# Sheet1.net
KiCad netlist of a schematic drawn in Altium Designer
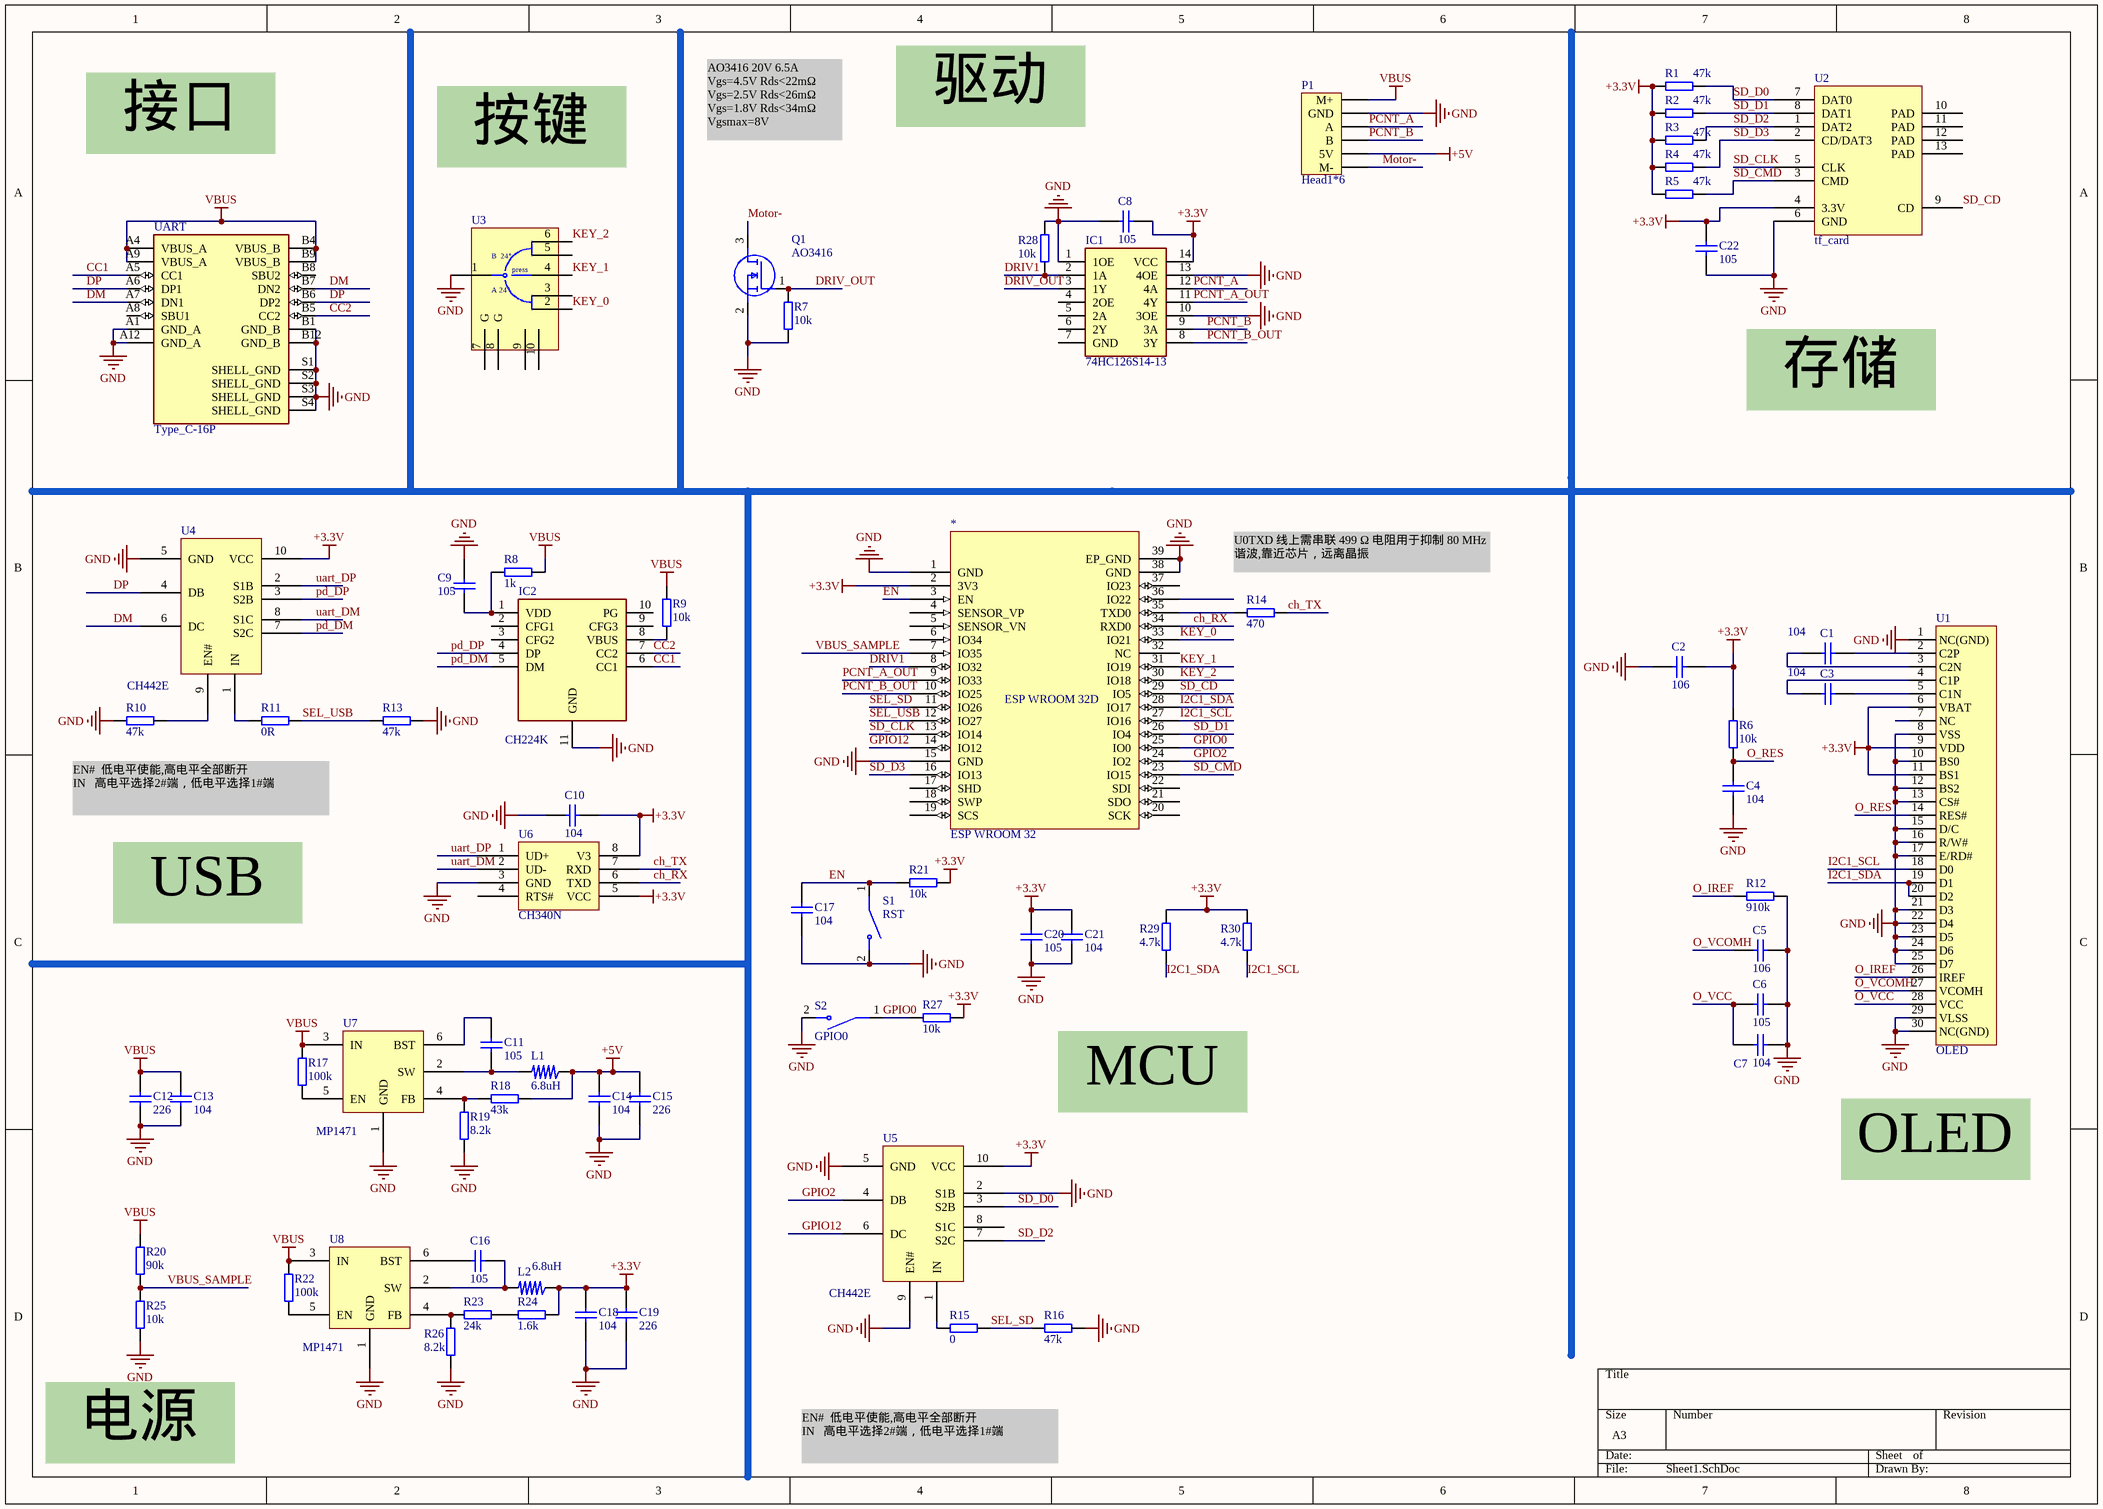
[diagram p0: Sheet1.SchDoc]

(export (version "E")
  (design (tool "Eeschema 10.0.6"))
  (components
    (comp (ref "*")
      (value "ESP WROOM 32")
      (footprint "ESP32-WROOM-32D")
      (libsource (lib "BuildDev") (part "ESP WROOM 32"))
    )
    (comp (ref "C1")
      (value "104")
      (footprint "CAPC1608[0603]")
      (description "Chip Capacitor, PSpice Model")
      (fields
        (field (name "TOLERANCE") "Y5V")
        (field (name "VOLTAGE") "3V")
        (field (name "PUBLISHER") "Altium Limited")
      )
      (libsource (lib "!)Miscellaneous Integrated Library") (part "Cap Chip 1"))
    )
    (comp (ref "C2")
      (value "106")
      (footprint "CAPC1608[0603]")
      (description "Chip Capacitor, PSpice Model")
      (fields
        (field (name "TOLERANCE") "Y5V")
        (field (name "VOLTAGE") "3V")
        (field (name "PUBLISHER") "Altium Limited")
      )
      (libsource (lib "!)Miscellaneous Integrated Library") (part "Cap Chip 1"))
    )
    (comp (ref "C3")
      (value "104")
      (footprint "CAPC1608[0603]")
      (description "Chip Capacitor, PSpice Model")
      (fields
        (field (name "TOLERANCE") "Y5V")
        (field (name "VOLTAGE") "3V")
        (field (name "PUBLISHER") "Altium Limited")
      )
      (libsource (lib "!)Miscellaneous Integrated Library") (part "Cap Chip 1"))
    )
    (comp (ref "C4")
      (value "104")
      (footprint "CAPC1608[0603]")
      (description "Chip Capacitor, PSpice Model")
      (fields
        (field (name "TOLERANCE") "Y5V")
        (field (name "VOLTAGE") "3V")
        (field (name "PUBLISHER") "Altium Limited")
      )
      (libsource (lib "!)Miscellaneous Integrated Library") (part "Cap Chip 1"))
    )
    (comp (ref "C5")
      (value "106")
      (footprint "CAPC1608[0603]")
      (description "Chip Capacitor, PSpice Model")
      (fields
        (field (name "TOLERANCE") "Y5V")
        (field (name "VOLTAGE") "3V")
        (field (name "PUBLISHER") "Altium Limited")
      )
      (libsource (lib "!)Miscellaneous Integrated Library") (part "Cap Chip 1"))
    )
    (comp (ref "C6")
      (value "105")
      (footprint "CAPC1608[0603]")
      (description "Chip Capacitor, PSpice Model")
      (fields
        (field (name "TOLERANCE") "Y5V")
        (field (name "VOLTAGE") "3V")
        (field (name "PUBLISHER") "Altium Limited")
      )
      (libsource (lib "!)Miscellaneous Integrated Library") (part "Cap Chip 1"))
    )
    (comp (ref "C7")
      (value "104")
      (footprint "CAPC1608[0603]")
      (description "Chip Capacitor, PSpice Model")
      (fields
        (field (name "TOLERANCE") "Y5V")
        (field (name "VOLTAGE") "3V")
        (field (name "PUBLISHER") "Altium Limited")
      )
      (libsource (lib "!)Miscellaneous Integrated Library") (part "Cap Chip 1"))
    )
    (comp (ref "C8")
      (value "105")
      (footprint "CAPC1608[0603]")
      (description "Chip Capacitor, PSpice Model")
      (fields
        (field (name "TOLERANCE") "Y5V")
        (field (name "VOLTAGE") "3V")
        (field (name "PUBLISHER") "Altium Limited")
      )
      (libsource (lib "!)Miscellaneous Integrated Library") (part "Cap Chip 1"))
    )
    (comp (ref "C9")
      (value "105")
      (footprint "CAPC1608[0603]")
      (description "Chip Capacitor, PSpice Model")
      (fields
        (field (name "TOLERANCE") "Y5V")
        (field (name "VOLTAGE") "3V")
        (field (name "PUBLISHER") "Altium Limited")
      )
      (libsource (lib "!)Miscellaneous Integrated Library") (part "Cap Chip 1"))
    )
    (comp (ref "C10")
      (value "104")
      (footprint "CAPC1608[0603]")
      (description "Chip Capacitor, PSpice Model")
      (fields
        (field (name "TOLERANCE") "Y5V")
        (field (name "VOLTAGE") "3V")
        (field (name "PUBLISHER") "Altium Limited")
      )
      (libsource (lib "!)Miscellaneous Integrated Library") (part "Cap Chip 1"))
    )
    (comp (ref "C11")
      (value "105")
      (footprint "CAPC1608[0603]")
      (description "Chip Capacitor, PSpice Model")
      (fields
        (field (name "TOLERANCE") "Y5V")
        (field (name "VOLTAGE") "3V")
        (field (name "PUBLISHER") "Altium Limited")
      )
      (libsource (lib "!)Miscellaneous Integrated Library") (part "Cap Chip 1"))
    )
    (comp (ref "C12")
      (value "226")
      (footprint "CAPC1608[0603]")
      (description "Chip Capacitor, PSpice Model")
      (fields
        (field (name "TOLERANCE") "Y5V")
        (field (name "VOLTAGE") "3V")
        (field (name "PUBLISHER") "Altium Limited")
      )
      (libsource (lib "!)Miscellaneous Integrated Library") (part "Cap Chip 1"))
    )
    (comp (ref "C13")
      (value "104")
      (footprint "CAPC1608[0603]")
      (description "Chip Capacitor, PSpice Model")
      (fields
        (field (name "TOLERANCE") "Y5V")
        (field (name "VOLTAGE") "3V")
        (field (name "PUBLISHER") "Altium Limited")
      )
      (libsource (lib "!)Miscellaneous Integrated Library") (part "Cap Chip 1"))
    )
    (comp (ref "C14")
      (value "104")
      (footprint "CAPC1608[0603]")
      (description "Chip Capacitor, PSpice Model")
      (fields
        (field (name "TOLERANCE") "Y5V")
        (field (name "VOLTAGE") "3V")
        (field (name "PUBLISHER") "Altium Limited")
      )
      (libsource (lib "!)Miscellaneous Integrated Library") (part "Cap Chip 1"))
    )
    (comp (ref "C15")
      (value "226")
      (footprint "CAPC1608[0603]")
      (description "Chip Capacitor, PSpice Model")
      (fields
        (field (name "TOLERANCE") "Y5V")
        (field (name "VOLTAGE") "3V")
        (field (name "PUBLISHER") "Altium Limited")
      )
      (libsource (lib "!)Miscellaneous Integrated Library") (part "Cap Chip 1"))
    )
    (comp (ref "C16")
      (value "105")
      (footprint "CAPC1608[0603]")
      (description "Chip Capacitor, PSpice Model")
      (fields
        (field (name "TOLERANCE") "Y5V")
        (field (name "VOLTAGE") "3V")
        (field (name "PUBLISHER") "Altium Limited")
      )
      (libsource (lib "!)Miscellaneous Integrated Library") (part "Cap Chip 1"))
    )
    (comp (ref "C17")
      (value "104")
      (footprint "CAPC1608[0603]")
      (description "Chip Capacitor, PSpice Model")
      (fields
        (field (name "TOLERANCE") "Y5V")
        (field (name "VOLTAGE") "3V")
        (field (name "PUBLISHER") "Altium Limited")
      )
      (libsource (lib "!)Miscellaneous Integrated Library") (part "Cap Chip 1"))
    )
    (comp (ref "C18")
      (value "104")
      (footprint "CAPC1608[0603]")
      (description "Chip Capacitor, PSpice Model")
      (fields
        (field (name "TOLERANCE") "Y5V")
        (field (name "VOLTAGE") "3V")
        (field (name "PUBLISHER") "Altium Limited")
      )
      (libsource (lib "!)Miscellaneous Integrated Library") (part "Cap Chip 1"))
    )
    (comp (ref "C19")
      (value "226")
      (footprint "CAPC1608[0603]")
      (description "Chip Capacitor, PSpice Model")
      (fields
        (field (name "TOLERANCE") "Y5V")
        (field (name "VOLTAGE") "3V")
        (field (name "PUBLISHER") "Altium Limited")
      )
      (libsource (lib "!)Miscellaneous Integrated Library") (part "Cap Chip 1"))
    )
    (comp (ref "C20")
      (value "105")
      (footprint "CAPC1608[0603]")
      (description "Chip Capacitor, PSpice Model")
      (fields
        (field (name "TOLERANCE") "Y5V")
        (field (name "VOLTAGE") "3V")
        (field (name "PUBLISHER") "Altium Limited")
      )
      (libsource (lib "!)Miscellaneous Integrated Library") (part "Cap Chip 1"))
    )
    (comp (ref "C21")
      (value "104")
      (footprint "CAPC1608[0603]")
      (description "Chip Capacitor, PSpice Model")
      (fields
        (field (name "TOLERANCE") "Y5V")
        (field (name "VOLTAGE") "3V")
        (field (name "PUBLISHER") "Altium Limited")
      )
      (libsource (lib "!)Miscellaneous Integrated Library") (part "Cap Chip 1"))
    )
    (comp (ref "C22")
      (value "105")
      (footprint "CAPC1608[0603]")
      (description "Chip Capacitor, PSpice Model")
      (fields
        (field (name "TOLERANCE") "Y5V")
        (field (name "VOLTAGE") "3V")
        (field (name "PUBLISHER") "Altium Limited")
      )
      (libsource (lib "!)Miscellaneous Integrated Library") (part "Cap Chip 1"))
    )
    (comp (ref "IC1")
      (value "74HC126S14-13")
      (footprint "SOIC127P600X173-14N")
      (description "Integrated Circuit")
      (fields (field (name "MOUSER PART NUMBER") "621-74HC126S14-13"))
      (libsource (lib "SamacSys") (part "74HC126S14-13"))
    )
    (comp (ref "IC2")
      (value "CH224K")
      (footprint "SOP100P600X180-11N")
      (description "Integrated Circuit")
      (libsource (lib "SamacSys") (part "CH224K"))
    )
    (comp (ref "L1") (value "6.8uH") (footprint "WHC0420") (libsource (lib "BuildDev") (part "L")))
    (comp (ref "L2") (value "6.8uH") (footprint "WHC0420") (libsource (lib "BuildDev") (part "L")))
    (comp (ref "P1")
      (value "Head1*6")
      (footprint "Header1*6")
      (libsource (lib "BuildDev") (part "Header1x6"))
    )
    (comp (ref "Q1")
      (value "AO3416")
      (footprint "SOT95P237X112-3N")
      (description "MOSFET (N-Channel)")
      (libsource (lib "SamacSys") (part "AO3416"))
    )
    (comp (ref "R1")
      (value "47k")
      (footprint "RESC1608[0603]")
      (description "Chip Resistor, PSpice Model, IPC PCB Library Drawing")
      (fields (field (name "TOLERANCE") "5%") (field (name "PUBLISHER") "Altium Limited"))
      (libsource (lib "!)Miscellaneous Integrated Library") (part "Res Chip 2p 1"))
    )
    (comp (ref "R2")
      (value "47k")
      (footprint "RESC1608[0603]")
      (description "Chip Resistor, PSpice Model, IPC PCB Library Drawing")
      (fields (field (name "TOLERANCE") "5%") (field (name "PUBLISHER") "Altium Limited"))
      (libsource (lib "!)Miscellaneous Integrated Library") (part "Res Chip 2p 1"))
    )
    (comp (ref "R3")
      (value "47k")
      (footprint "RESC1608[0603]")
      (description "Chip Resistor, PSpice Model, IPC PCB Library Drawing")
      (fields (field (name "TOLERANCE") "5%") (field (name "PUBLISHER") "Altium Limited"))
      (libsource (lib "!)Miscellaneous Integrated Library") (part "Res Chip 2p 1"))
    )
    (comp (ref "R4")
      (value "47k")
      (footprint "RESC1608[0603]")
      (description "Chip Resistor, PSpice Model, IPC PCB Library Drawing")
      (fields (field (name "TOLERANCE") "5%") (field (name "PUBLISHER") "Altium Limited"))
      (libsource (lib "!)Miscellaneous Integrated Library") (part "Res Chip 2p 1"))
    )
    (comp (ref "R5")
      (value "47k")
      (footprint "RESC1608[0603]")
      (description "Chip Resistor, PSpice Model, IPC PCB Library Drawing")
      (fields (field (name "TOLERANCE") "5%") (field (name "PUBLISHER") "Altium Limited"))
      (libsource (lib "!)Miscellaneous Integrated Library") (part "Res Chip 2p 1"))
    )
    (comp (ref "R6")
      (value "10k")
      (footprint "RESC1608[0603]")
      (description "Chip Resistor, PSpice Model, IPC PCB Library Drawing")
      (fields (field (name "TOLERANCE") "5%") (field (name "PUBLISHER") "Altium Limited"))
      (libsource (lib "!)Miscellaneous Integrated Library") (part "Res Chip 2p 1"))
    )
    (comp (ref "R7")
      (value "10k")
      (footprint "RESC1608[0603]")
      (description "Chip Resistor, PSpice Model, IPC PCB Library Drawing")
      (fields (field (name "TOLERANCE") "5%") (field (name "PUBLISHER") "Altium Limited"))
      (libsource (lib "!)Miscellaneous Integrated Library") (part "Res Chip 2p 1"))
    )
    (comp (ref "R8")
      (value "1k")
      (footprint "RESC1608[0603]")
      (description "Chip Resistor, PSpice Model, IPC PCB Library Drawing")
      (fields (field (name "TOLERANCE") "5%") (field (name "PUBLISHER") "Altium Limited"))
      (libsource (lib "!)Miscellaneous Integrated Library") (part "Res Chip 2p 1"))
    )
    (comp (ref "R9")
      (value "10k")
      (footprint "RESC1608[0603]")
      (description "Chip Resistor, PSpice Model, IPC PCB Library Drawing")
      (fields (field (name "TOLERANCE") "5%") (field (name "PUBLISHER") "Altium Limited"))
      (libsource (lib "!)Miscellaneous Integrated Library") (part "Res Chip 2p 1"))
    )
    (comp (ref "R10")
      (value "47k")
      (footprint "RESC1608[0603]")
      (description "Chip Resistor, PSpice Model, IPC PCB Library Drawing")
      (fields (field (name "TOLERANCE") "5%") (field (name "PUBLISHER") "Altium Limited"))
      (libsource (lib "!)Miscellaneous Integrated Library") (part "Res Chip 2p 1"))
    )
    (comp (ref "R11")
      (value "0R")
      (footprint "RESC1608[0603]")
      (description "Chip Resistor, PSpice Model, IPC PCB Library Drawing")
      (fields (field (name "TOLERANCE") "5%") (field (name "PUBLISHER") "Altium Limited"))
      (libsource (lib "!)Miscellaneous Integrated Library") (part "Res Chip 2p 1"))
    )
    (comp (ref "R12")
      (value "910k")
      (footprint "RESC1608[0603]")
      (description "Chip Resistor, PSpice Model, IPC PCB Library Drawing")
      (fields (field (name "TOLERANCE") "5%") (field (name "PUBLISHER") "Altium Limited"))
      (libsource (lib "!)Miscellaneous Integrated Library") (part "Res Chip 2p 1"))
    )
    (comp (ref "R13")
      (value "47k")
      (footprint "RESC1608[0603]")
      (description "Chip Resistor, PSpice Model, IPC PCB Library Drawing")
      (fields (field (name "TOLERANCE") "5%") (field (name "PUBLISHER") "Altium Limited"))
      (libsource (lib "!)Miscellaneous Integrated Library") (part "Res Chip 2p 1"))
    )
    (comp (ref "R14")
      (value "470")
      (footprint "RESC1608[0603]")
      (description "Chip Resistor, PSpice Model, IPC PCB Library Drawing")
      (fields (field (name "TOLERANCE") "5%") (field (name "PUBLISHER") "Altium Limited"))
      (libsource (lib "!)Miscellaneous Integrated Library") (part "Res Chip 2p 1"))
    )
    (comp (ref "R15")
      (value "0")
      (footprint "RESC1608[0603]")
      (description "Chip Resistor, PSpice Model, IPC PCB Library Drawing")
      (fields (field (name "TOLERANCE") "5%") (field (name "PUBLISHER") "Altium Limited"))
      (libsource (lib "!)Miscellaneous Integrated Library") (part "Res Chip 2p 1"))
    )
    (comp (ref "R16")
      (value "47k")
      (footprint "RESC1608[0603]")
      (description "Chip Resistor, PSpice Model, IPC PCB Library Drawing")
      (fields (field (name "TOLERANCE") "5%") (field (name "PUBLISHER") "Altium Limited"))
      (libsource (lib "!)Miscellaneous Integrated Library") (part "Res Chip 2p 1"))
    )
    (comp (ref "R17")
      (value "100k")
      (footprint "RESC1608[0603]")
      (description "Chip Resistor, PSpice Model, IPC PCB Library Drawing")
      (fields (field (name "TOLERANCE") "5%") (field (name "PUBLISHER") "Altium Limited"))
      (libsource (lib "!)Miscellaneous Integrated Library") (part "Res Chip 2p 1"))
    )
    (comp (ref "R18")
      (value "43k")
      (footprint "RESC1608[0603]")
      (description "Chip Resistor, PSpice Model, IPC PCB Library Drawing")
      (fields (field (name "TOLERANCE") "5%") (field (name "PUBLISHER") "Altium Limited"))
      (libsource (lib "!)Miscellaneous Integrated Library") (part "Res Chip 2p 1"))
    )
    (comp (ref "R19")
      (value "8.2k")
      (footprint "RESC1608[0603]")
      (description "Chip Resistor, PSpice Model, IPC PCB Library Drawing")
      (fields (field (name "TOLERANCE") "5%") (field (name "PUBLISHER") "Altium Limited"))
      (libsource (lib "!)Miscellaneous Integrated Library") (part "Res Chip 2p 1"))
    )
    (comp (ref "R20")
      (value "90k")
      (footprint "RESC1608[0603]")
      (description "Chip Resistor, PSpice Model, IPC PCB Library Drawing")
      (fields (field (name "TOLERANCE") "5%") (field (name "PUBLISHER") "Altium Limited"))
      (libsource (lib "!)Miscellaneous Integrated Library") (part "Res Chip 2p 1"))
    )
    (comp (ref "R21")
      (value "10k")
      (footprint "RESC1608[0603]")
      (description "Chip Resistor, PSpice Model, IPC PCB Library Drawing")
      (fields (field (name "TOLERANCE") "5%") (field (name "PUBLISHER") "Altium Limited"))
      (libsource (lib "!)Miscellaneous Integrated Library") (part "Res Chip 2p 1"))
    )
    (comp (ref "R22")
      (value "100k")
      (footprint "RESC1608[0603]")
      (description "Chip Resistor, PSpice Model, IPC PCB Library Drawing")
      (fields (field (name "TOLERANCE") "5%") (field (name "PUBLISHER") "Altium Limited"))
      (libsource (lib "!)Miscellaneous Integrated Library") (part "Res Chip 2p 1"))
    )
    (comp (ref "R23")
      (value "24k")
      (footprint "RESC1608[0603]")
      (description "Chip Resistor, PSpice Model, IPC PCB Library Drawing")
      (fields (field (name "TOLERANCE") "5%") (field (name "PUBLISHER") "Altium Limited"))
      (libsource (lib "!)Miscellaneous Integrated Library") (part "Res Chip 2p 1"))
    )
    (comp (ref "R24")
      (value "1.6k")
      (footprint "RESC1608[0603]")
      (description "Chip Resistor, PSpice Model, IPC PCB Library Drawing")
      (fields (field (name "TOLERANCE") "5%") (field (name "PUBLISHER") "Altium Limited"))
      (libsource (lib "!)Miscellaneous Integrated Library") (part "Res Chip 2p 1"))
    )
    (comp (ref "R25")
      (value "10k")
      (footprint "RESC1608[0603]")
      (description "Chip Resistor, PSpice Model, IPC PCB Library Drawing")
      (fields (field (name "TOLERANCE") "5%") (field (name "PUBLISHER") "Altium Limited"))
      (libsource (lib "!)Miscellaneous Integrated Library") (part "Res Chip 2p 1"))
    )
    (comp (ref "R26")
      (value "8.2k")
      (footprint "RESC1608[0603]")
      (description "Chip Resistor, PSpice Model, IPC PCB Library Drawing")
      (fields (field (name "TOLERANCE") "5%") (field (name "PUBLISHER") "Altium Limited"))
      (libsource (lib "!)Miscellaneous Integrated Library") (part "Res Chip 2p 1"))
    )
    (comp (ref "R27")
      (value "10k")
      (footprint "RESC1608[0603]")
      (description "Chip Resistor, PSpice Model, IPC PCB Library Drawing")
      (fields (field (name "TOLERANCE") "5%") (field (name "PUBLISHER") "Altium Limited"))
      (libsource (lib "!)Miscellaneous Integrated Library") (part "Res Chip 2p 1"))
    )
    (comp (ref "R28")
      (value "10k")
      (footprint "RESC1608[0603]")
      (description "Chip Resistor, PSpice Model, IPC PCB Library Drawing")
      (fields (field (name "TOLERANCE") "5%") (field (name "PUBLISHER") "Altium Limited"))
      (libsource (lib "!)Miscellaneous Integrated Library") (part "Res Chip 2p 1"))
    )
    (comp (ref "R29")
      (value "4.7k")
      (footprint "RESC1608[0603]")
      (description "Chip Resistor, PSpice Model, IPC PCB Library Drawing")
      (fields (field (name "TOLERANCE") "5%") (field (name "PUBLISHER") "Altium Limited"))
      (libsource (lib "!)Miscellaneous Integrated Library") (part "Res Chip 2p 1"))
    )
    (comp (ref "R30")
      (value "4.7k")
      (footprint "RESC1608[0603]")
      (description "Chip Resistor, PSpice Model, IPC PCB Library Drawing")
      (fields (field (name "TOLERANCE") "5%") (field (name "PUBLISHER") "Altium Limited"))
      (libsource (lib "!)Miscellaneous Integrated Library") (part "Res Chip 2p 1"))
    )
    (comp (ref "S1")
      (value "RST")
      (footprint "SW_B3U-1000P")
      (fields (field (name "MP") "B3U-1000P"))
      (libsource (lib "BuildDev") (part "SW2P"))
    )
    (comp (ref "S2")
      (value "GPIO0")
      (footprint "SW_B3U-1000P")
      (fields (field (name "MP") "B3U-1000P"))
      (libsource (lib "BuildDev") (part "SW2P"))
    )
    (comp (ref "U1") (value "OLED") (footprint "OLED-panel") (libsource (lib "BuildDev") (part "0.96寸OLED")))
    (comp (ref "U2") (value "tf_card") (footprint "TF-1") (libsource (lib "BuildDev") (part "TF- SDIO")))
    (comp (ref "U3") (value "拨码开关") (footprint "FS-1501S-02") (libsource (lib "BuildDev") (part "thumb key")))
    (comp (ref "U4") (value "CH442E") (footprint "MSOP-10") (libsource (lib "BuildDev") (part "CH442E")))
    (comp (ref "U5") (value "CH442E") (footprint "MSOP-10") (libsource (lib "BuildDev") (part "CH442E")))
    (comp (ref "U6")
      (value "CH340N")
      (footprint "SOP8")
      (description "USB to serial chip CH340N")
      (libsource (lib "BuildDev") (part "CH340N"))
    )
    (comp (ref "U7")
      (value "MP1471")
      (footprint "TSOT23-6")
      (description "4.7v-16V Input\r\n16V3A\r\n500K")
      (libsource (lib "BuildDev") (part "MP1471"))
    )
    (comp (ref "U8")
      (value "MP1471")
      (footprint "TSOT23-6")
      (description "4.7v-16V Input\r\n16V3A\r\n500K")
      (libsource (lib "BuildDev") (part "MP1471"))
    )
    (comp (ref "UART")
      (value "Type_C-16P")
      (footprint "VALCON_CSP-USC16-TR")
      (description "CSP-USC16-TR Valcon USB Type C Surface Mount PCB Socket")
      (fields (field (name "MP") "CSP-USC16-TR") (field (name "MF") "Valcon"))
      (libsource (lib "BuildDev") (part "Type_C-16P"))
    )
  )
  (nets
    (net (code "1") (name "+3.3V") (class "Default")
      (node (ref "*") (pin "2") (pinfunction "3V3_2") (pintype "passive"))
      (node (ref "C10") (pin "1") (pinfunction "1_1") (pintype "passive"))
      (node (ref "C18") (pin "1") (pinfunction "1_1") (pintype "passive"))
      (node (ref "C19") (pin "1") (pinfunction "1_1") (pintype "passive"))
      (node (ref "C2") (pin "1") (pinfunction "1_1") (pintype "passive"))
      (node (ref "C20") (pin "1") (pinfunction "1_1") (pintype "passive"))
      (node (ref "C21") (pin "1") (pinfunction "1_1") (pintype "passive"))
      (node (ref "C22") (pin "2") (pinfunction "2_2") (pintype "passive"))
      (node (ref "C8") (pin "2") (pinfunction "2_2") (pintype "passive"))
      (node (ref "IC1") (pin "14") (pinfunction "VCC_14") (pintype "passive"))
      (node (ref "L2") (pin "1") (pinfunction "1_1") (pintype "passive"))
      (node (ref "R1") (pin "2") (pinfunction "2_2") (pintype "passive"))
      (node (ref "R2") (pin "2") (pinfunction "2_2") (pintype "passive"))
      (node (ref "R21") (pin "1") (pinfunction "1_1") (pintype "passive"))
      (node (ref "R24") (pin "2") (pinfunction "2_2") (pintype "passive"))
      (node (ref "R27") (pin "1") (pinfunction "1_1") (pintype "passive"))
      (node (ref "R29") (pin "1") (pinfunction "1_1") (pintype "passive"))
      (node (ref "R3") (pin "2") (pinfunction "2_2") (pintype "passive"))
      (node (ref "R30") (pin "1") (pinfunction "1_1") (pintype "passive"))
      (node (ref "R4") (pin "2") (pinfunction "2_2") (pintype "passive"))
      (node (ref "R5") (pin "2") (pinfunction "2_2") (pintype "passive"))
      (node (ref "R6") (pin "1") (pinfunction "1_1") (pintype "passive"))
      (node (ref "U1") (pin "11") (pinfunction "BS1_11") (pintype "passive"))
      (node (ref "U1") (pin "6") (pinfunction "VBAT_6") (pintype "passive"))
      (node (ref "U1") (pin "9") (pinfunction "VDD_9") (pintype "passive"))
      (node (ref "U2") (pin "4") (pinfunction "3.3V_4") (pintype "passive"))
      (node (ref "U4") (pin "10") (pinfunction "VCC_10") (pintype "passive"))
      (node (ref "U5") (pin "10") (pinfunction "VCC_10") (pintype "passive"))
      (node (ref "U6") (pin "5") (pinfunction "VCC_5") (pintype "passive"))
      (node (ref "U6") (pin "8") (pinfunction "V3_8") (pintype "passive"))
    )
    (net (code "2") (name "+5V") (class "Default")
      (node (ref "C14") (pin "1") (pinfunction "1_1") (pintype "passive"))
      (node (ref "C15") (pin "1") (pinfunction "1_1") (pintype "passive"))
      (node (ref "L1") (pin "1") (pinfunction "1_1") (pintype "passive"))
      (node (ref "P1") (pin "5") (pinfunction "5V_5") (pintype "passive"))
      (node (ref "R18") (pin "2") (pinfunction "2_2") (pintype "passive"))
    )
    (net (code "3") (name "/CC1") (class "Default")
      (node (ref "IC2") (pin "6") (pinfunction "CC1_6") (pintype "passive"))
      (node (ref "UART") (pin "A5") (pinfunction "CC1_A5") (pintype "bidirectional"))
    )
    (net (code "4") (name "/CC2") (class "Default")
      (node (ref "IC2") (pin "7") (pinfunction "CC2_7") (pintype "passive"))
      (node (ref "UART") (pin "B5") (pinfunction "CC2_B5") (pintype "bidirectional"))
    )
    (net (code "5") (name "/DM") (class "Default")
      (node (ref "U4") (pin "6") (pinfunction "DC_6") (pintype "passive"))
      (node (ref "UART") (pin "A7") (pinfunction "DN1_A7") (pintype "bidirectional"))
      (node (ref "UART") (pin "B7") (pinfunction "DN2_B7") (pintype "bidirectional"))
    )
    (net (code "6") (name "/DP") (class "Default")
      (node (ref "U4") (pin "4") (pinfunction "DB_4") (pintype "passive"))
      (node (ref "UART") (pin "A6") (pinfunction "DP1_A6") (pintype "bidirectional"))
      (node (ref "UART") (pin "B6") (pinfunction "DP2_B6") (pintype "bidirectional"))
    )
    (net (code "7") (name "/DRIV1") (class "Default")
      (node (ref "*") (pin "8") (pinfunction "IO32_8") (pintype "bidirectional"))
      (node (ref "IC1") (pin "2") (pinfunction "1A_2") (pintype "passive"))
      (node (ref "R28") (pin "2") (pinfunction "2_2") (pintype "passive"))
    )
    (net (code "8") (name "/DRIV_OUT") (class "Default")
      (node (ref "IC1") (pin "3") (pinfunction "1Y_3") (pintype "passive"))
      (node (ref "Q1") (pin "1") (pinfunction "G_1") (pintype "passive"))
      (node (ref "R7") (pin "2") (pinfunction "2_2") (pintype "passive"))
    )
    (net (code "9") (name "/EN") (class "Default")
      (node (ref "*") (pin "3") (pinfunction "EN_3") (pintype "input"))
      (node (ref "C17") (pin "1") (pinfunction "1_1") (pintype "passive"))
      (node (ref "R21") (pin "2") (pinfunction "2_2") (pintype "passive"))
      (node (ref "S1") (pin "1") (pinfunction "1_1") (pintype "passive"))
    )
    (net (code "10") (name "/GPIO0") (class "Default")
      (node (ref "*") (pin "25") (pinfunction "IO0_25") (pintype "bidirectional"))
      (node (ref "R27") (pin "2") (pinfunction "2_2") (pintype "passive"))
      (node (ref "S2") (pin "1") (pinfunction "1_1") (pintype "passive"))
    )
    (net (code "11") (name "/GPIO2") (class "Default")
      (node (ref "*") (pin "24") (pinfunction "IO2_24") (pintype "bidirectional"))
      (node (ref "U5") (pin "4") (pinfunction "DB_4") (pintype "passive"))
    )
    (net (code "12") (name "/GPIO12") (class "Default")
      (node (ref "*") (pin "14") (pinfunction "IO12_14") (pintype "bidirectional"))
      (node (ref "U5") (pin "6") (pinfunction "DC_6") (pintype "passive"))
    )
    (net (code "13") (name "/I2C1_SCL") (class "Default")
      (node (ref "*") (pin "27") (pinfunction "IO16_27") (pintype "bidirectional"))
      (node (ref "R30") (pin "2") (pinfunction "2_2") (pintype "passive"))
      (node (ref "U1") (pin "18") (pinfunction "D0_18") (pintype "passive"))
    )
    (net (code "14") (name "/I2C1_SDA") (class "Default")
      (node (ref "*") (pin "28") (pinfunction "IO17_28") (pintype "bidirectional"))
      (node (ref "R29") (pin "2") (pinfunction "2_2") (pintype "passive"))
      (node (ref "U1") (pin "19") (pinfunction "D1_19") (pintype "passive"))
      (node (ref "U1") (pin "20") (pinfunction "D2_20") (pintype "passive"))
    )
    (net (code "15") (name "/KEY_0") (class "Default")
      (node (ref "*") (pin "33") (pinfunction "IO21_33") (pintype "bidirectional"))
      (node (ref "U3") (pin "2") (pintype "passive"))
    )
    (net (code "16") (name "/KEY_1") (class "Default")
      (node (ref "*") (pin "31") (pinfunction "IO19_31") (pintype "bidirectional"))
      (node (ref "U3") (pin "4") (pintype "passive"))
    )
    (net (code "17") (name "/KEY_2") (class "Default")
      (node (ref "*") (pin "30") (pinfunction "IO18_30") (pintype "bidirectional"))
      (node (ref "U3") (pin "6") (pintype "passive"))
    )
    (net (code "18") (name "/Motor-") (class "Default")
      (node (ref "P1") (pin "6") (pinfunction "M-_6") (pintype "passive"))
      (node (ref "Q1") (pin "3") (pinfunction "D_3") (pintype "passive"))
    )
    (net (code "19") (name "/O_IREF") (class "Default")
      (node (ref "R12") (pin "1") (pinfunction "1_1") (pintype "passive"))
      (node (ref "U1") (pin "26") (pinfunction "IREF_26") (pintype "passive"))
    )
    (net (code "20") (name "/O_RES") (class "Default")
      (node (ref "C4") (pin "1") (pinfunction "1_1") (pintype "passive"))
      (node (ref "R6") (pin "2") (pinfunction "2_2") (pintype "passive"))
      (node (ref "U1") (pin "14") (pinfunction "RES#_14") (pintype "passive"))
    )
    (net (code "21") (name "/O_VCC") (class "Default")
      (node (ref "C6") (pin "2") (pinfunction "2_2") (pintype "passive"))
      (node (ref "C7") (pin "1") (pinfunction "1_1") (pintype "passive"))
      (node (ref "U1") (pin "28") (pinfunction "VCC_28") (pintype "passive"))
    )
    (net (code "22") (name "/O_VCOMH") (class "Default")
      (node (ref "C5") (pin "1") (pinfunction "1_1") (pintype "passive"))
      (node (ref "U1") (pin "27") (pinfunction "VCOMH_27") (pintype "passive"))
    )
    (net (code "23") (name "/PCNT_A") (class "Default")
      (node (ref "IC1") (pin "12") (pinfunction "4A_12") (pintype "passive"))
      (node (ref "P1") (pin "3") (pinfunction "A_3") (pintype "passive"))
    )
    (net (code "24") (name "/PCNT_A_OUT") (class "Default")
      (node (ref "*") (pin "9") (pinfunction "IO33_9") (pintype "bidirectional"))
      (node (ref "IC1") (pin "11") (pinfunction "4Y_11") (pintype "passive"))
    )
    (net (code "25") (name "/PCNT_B") (class "Default")
      (node (ref "IC1") (pin "9") (pinfunction "3A_9") (pintype "passive"))
      (node (ref "P1") (pin "4") (pinfunction "B_4") (pintype "passive"))
    )
    (net (code "26") (name "/PCNT_B_OUT") (class "Default")
      (node (ref "*") (pin "10") (pinfunction "IO25_10") (pintype "bidirectional"))
      (node (ref "IC1") (pin "8") (pinfunction "3Y_8") (pintype "passive"))
    )
    (net (code "27") (name "/SD_CD") (class "Default")
      (node (ref "*") (pin "29") (pinfunction "IO5_29") (pintype "bidirectional"))
      (node (ref "U2") (pin "9") (pinfunction "CD_9") (pintype "passive"))
    )
    (net (code "28") (name "/SD_CLK") (class "Default")
      (node (ref "*") (pin "13") (pinfunction "IO14_13") (pintype "bidirectional"))
      (node (ref "U2") (pin "5") (pinfunction "CLK_5") (pintype "passive"))
    )
    (net (code "29") (name "/SD_CMD") (class "Default")
      (node (ref "*") (pin "23") (pinfunction "IO15_23") (pintype "bidirectional"))
      (node (ref "R5") (pin "1") (pinfunction "1_1") (pintype "passive"))
      (node (ref "U2") (pin "3") (pinfunction "CMD_3") (pintype "passive"))
    )
    (net (code "30") (name "/SD_D0") (class "Default")
      (node (ref "R1") (pin "1") (pinfunction "1_1") (pintype "passive"))
      (node (ref "U2") (pin "7") (pinfunction "DAT0_7") (pintype "passive"))
      (node (ref "U5") (pin "3") (pinfunction "S2B_3") (pintype "passive"))
    )
    (net (code "31") (name "/SD_D1") (class "Default")
      (node (ref "*") (pin "26") (pinfunction "IO4_26") (pintype "bidirectional"))
      (node (ref "R2") (pin "1") (pinfunction "1_1") (pintype "passive"))
      (node (ref "U2") (pin "8") (pinfunction "DAT1_8") (pintype "passive"))
    )
    (net (code "32") (name "/SD_D2") (class "Default")
      (node (ref "R3") (pin "1") (pinfunction "1_1") (pintype "passive"))
      (node (ref "U2") (pin "1") (pinfunction "DAT2_1") (pintype "passive"))
      (node (ref "U5") (pin "7") (pinfunction "S2C_7") (pintype "passive"))
    )
    (net (code "33") (name "/SD_D3") (class "Default")
      (node (ref "*") (pin "16") (pinfunction "IO13_16") (pintype "bidirectional"))
      (node (ref "R4") (pin "1") (pinfunction "1_1") (pintype "passive"))
      (node (ref "U2") (pin "2") (pinfunction "CD/DAT3_2") (pintype "passive"))
    )
    (net (code "34") (name "/SEL_SD") (class "Default")
      (node (ref "*") (pin "11") (pinfunction "IO26_11") (pintype "bidirectional"))
      (node (ref "R15") (pin "1") (pinfunction "1_1") (pintype "passive"))
      (node (ref "R16") (pin "2") (pinfunction "2_2") (pintype "passive"))
    )
    (net (code "35") (name "/SEL_USB") (class "Default")
      (node (ref "*") (pin "12") (pinfunction "IO27_12") (pintype "bidirectional"))
      (node (ref "R11") (pin "1") (pinfunction "1_1") (pintype "passive"))
      (node (ref "R13") (pin "2") (pinfunction "2_2") (pintype "passive"))
    )
    (net (code "36") (name "/VBUS_SAMPLE") (class "Default")
      (node (ref "*") (pin "7") (pinfunction "IO35_7") (pintype "input"))
      (node (ref "R20") (pin "2") (pinfunction "2_2") (pintype "passive"))
      (node (ref "R25") (pin "1") (pinfunction "1_1") (pintype "passive"))
    )
    (net (code "37") (name "/ch_RX") (class "Default")
      (node (ref "*") (pin "34") (pinfunction "RXD0_34") (pintype "bidirectional"))
      (node (ref "U6") (pin "6") (pinfunction "TXD_6") (pintype "passive"))
    )
    (net (code "38") (name "/ch_TX") (class "Default")
      (node (ref "R14") (pin "1") (pinfunction "1_1") (pintype "passive"))
      (node (ref "U6") (pin "7") (pinfunction "RXD_7") (pintype "passive"))
    )
    (net (code "39") (name "/pd_DM") (class "Default")
      (node (ref "IC2") (pin "5") (pinfunction "DM_5") (pintype "passive"))
      (node (ref "U4") (pin "7") (pinfunction "S2C_7") (pintype "passive"))
    )
    (net (code "40") (name "/pd_DP") (class "Default")
      (node (ref "IC2") (pin "4") (pinfunction "DP_4") (pintype "passive"))
      (node (ref "U4") (pin "3") (pinfunction "S2B_3") (pintype "passive"))
    )
    (net (code "41") (name "/uart_DM") (class "Default")
      (node (ref "U4") (pin "8") (pinfunction "S1C_8") (pintype "passive"))
      (node (ref "U6") (pin "2") (pinfunction "UD-_2") (pintype "passive"))
    )
    (net (code "42") (name "/uart_DP") (class "Default")
      (node (ref "U4") (pin "2") (pinfunction "S1B_2") (pintype "passive"))
      (node (ref "U6") (pin "1") (pinfunction "UD+_1") (pintype "passive"))
    )
    (net (code "43") (name "GND") (class "Default")
      (node (ref "*") (pin "1") (pinfunction "GND_1") (pintype "passive"))
      (node (ref "*") (pin "15") (pinfunction "GND_15") (pintype "passive"))
      (node (ref "*") (pin "38") (pinfunction "GND_38") (pintype "passive"))
      (node (ref "*") (pin "39") (pinfunction "EP_GND_39") (pintype "passive"))
      (node (ref "C10") (pin "2") (pinfunction "2_2") (pintype "passive"))
      (node (ref "C12") (pin "2") (pinfunction "2_2") (pintype "passive"))
      (node (ref "C13") (pin "2") (pinfunction "2_2") (pintype "passive"))
      (node (ref "C14") (pin "2") (pinfunction "2_2") (pintype "passive"))
      (node (ref "C15") (pin "2") (pinfunction "2_2") (pintype "passive"))
      (node (ref "C17") (pin "2") (pinfunction "2_2") (pintype "passive"))
      (node (ref "C18") (pin "2") (pinfunction "2_2") (pintype "passive"))
      (node (ref "C19") (pin "2") (pinfunction "2_2") (pintype "passive"))
      (node (ref "C2") (pin "2") (pinfunction "2_2") (pintype "passive"))
      (node (ref "C20") (pin "2") (pinfunction "2_2") (pintype "passive"))
      (node (ref "C21") (pin "2") (pinfunction "2_2") (pintype "passive"))
      (node (ref "C22") (pin "1") (pinfunction "1_1") (pintype "passive"))
      (node (ref "C4") (pin "2") (pinfunction "2_2") (pintype "passive"))
      (node (ref "C5") (pin "2") (pinfunction "2_2") (pintype "passive"))
      (node (ref "C6") (pin "1") (pinfunction "1_1") (pintype "passive"))
      (node (ref "C7") (pin "2") (pinfunction "2_2") (pintype "passive"))
      (node (ref "C8") (pin "1") (pinfunction "1_1") (pintype "passive"))
      (node (ref "C9") (pin "1") (pinfunction "1_1") (pintype "passive"))
      (node (ref "IC1") (pin "1") (pinfunction "1OE_1") (pintype "passive"))
      (node (ref "IC1") (pin "10") (pinfunction "3OE_10") (pintype "passive"))
      (node (ref "IC1") (pin "13") (pinfunction "4OE_13") (pintype "passive"))
      (node (ref "IC2") (pin "11") (pinfunction "GND_11") (pintype "passive"))
      (node (ref "P1") (pin "2") (pinfunction "GND_2") (pintype "passive"))
      (node (ref "Q1") (pin "2") (pinfunction "S_2") (pintype "passive"))
      (node (ref "R10") (pin "2") (pinfunction "2_2") (pintype "passive"))
      (node (ref "R12") (pin "2") (pinfunction "2_2") (pintype "passive"))
      (node (ref "R13") (pin "1") (pinfunction "1_1") (pintype "passive"))
      (node (ref "R16") (pin "1") (pinfunction "1_1") (pintype "passive"))
      (node (ref "R19") (pin "2") (pinfunction "2_2") (pintype "passive"))
      (node (ref "R25") (pin "2") (pinfunction "2_2") (pintype "passive"))
      (node (ref "R26") (pin "2") (pinfunction "2_2") (pintype "passive"))
      (node (ref "R28") (pin "1") (pinfunction "1_1") (pintype "passive"))
      (node (ref "R7") (pin "1") (pinfunction "1_1") (pintype "passive"))
      (node (ref "S1") (pin "2") (pinfunction "2_2") (pintype "passive"))
      (node (ref "S2") (pin "2") (pinfunction "2_2") (pintype "passive"))
      (node (ref "U1") (pin "1") (pinfunction "NC(GND)_1") (pintype "passive"))
      (node (ref "U1") (pin "10") (pinfunction "BS0_10") (pintype "passive"))
      (node (ref "U1") (pin "12") (pinfunction "BS2_12") (pintype "passive"))
      (node (ref "U1") (pin "13") (pinfunction "CS#_13") (pintype "passive"))
      (node (ref "U1") (pin "15") (pinfunction "D/C_15") (pintype "passive"))
      (node (ref "U1") (pin "16") (pinfunction "R/W#_16") (pintype "passive"))
      (node (ref "U1") (pin "17") (pinfunction "E/RD#_17") (pintype "passive"))
      (node (ref "U1") (pin "21") (pinfunction "D3_21") (pintype "passive"))
      (node (ref "U1") (pin "22") (pinfunction "D4_22") (pintype "passive"))
      (node (ref "U1") (pin "23") (pinfunction "D5_23") (pintype "passive"))
      (node (ref "U1") (pin "24") (pinfunction "D6_24") (pintype "passive"))
      (node (ref "U1") (pin "25") (pinfunction "D7_25") (pintype "passive"))
      (node (ref "U1") (pin "29") (pinfunction "VLSS_29") (pintype "passive"))
      (node (ref "U1") (pin "30") (pinfunction "NC(GND)_30") (pintype "passive"))
      (node (ref "U1") (pin "8") (pinfunction "VSS_8") (pintype "passive"))
      (node (ref "U2") (pin "6") (pinfunction "GND_6") (pintype "passive"))
      (node (ref "U3") (pin "1") (pintype "passive"))
      (node (ref "U4") (pin "5") (pinfunction "GND_5") (pintype "passive"))
      (node (ref "U5") (pin "2") (pinfunction "S1B_2") (pintype "passive"))
      (node (ref "U5") (pin "5") (pinfunction "GND_5") (pintype "passive"))
      (node (ref "U5") (pin "9") (pinfunction "EN#_9") (pintype "passive"))
      (node (ref "U6") (pin "3") (pinfunction "GND_3") (pintype "passive"))
      (node (ref "U7") (pin "1") (pinfunction "GND_1") (pintype "passive"))
      (node (ref "U8") (pin "1") (pinfunction "GND_1") (pintype "passive"))
      (node (ref "UART") (pin "A1") (pinfunction "GND_A_A1") (pintype "power_in"))
      (node (ref "UART") (pin "A12") (pinfunction "GND_A_A12") (pintype "power_in"))
      (node (ref "UART") (pin "B1") (pinfunction "GND_B_B1") (pintype "power_in"))
      (node (ref "UART") (pin "B12") (pinfunction "GND_B_B12") (pintype "power_in"))
      (node (ref "UART") (pin "S1") (pinfunction "SHELL_GND_S1") (pintype "power_in"))
      (node (ref "UART") (pin "S2") (pinfunction "SHELL_GND_S2") (pintype "power_in"))
      (node (ref "UART") (pin "S3") (pinfunction "SHELL_GND_S3") (pintype "power_in"))
      (node (ref "UART") (pin "S4") (pinfunction "SHELL_GND_S4") (pintype "power_in"))
    )
    (net (code "44") (name "Net-(*-TXD0)") (class "Default")
      (node (ref "*") (pin "35") (pinfunction "TXD0_35") (pintype "bidirectional"))
      (node (ref "R14") (pin "2") (pinfunction "2_2") (pintype "passive"))
    )
    (net (code "45") (name "Net-(IC2-VBUS)") (class "Default")
      (node (ref "IC2") (pin "8") (pinfunction "VBUS_8") (pintype "passive"))
      (node (ref "R9") (pin "1") (pinfunction "1_1") (pintype "passive"))
    )
    (net (code "46") (name "Net-(IC2-VDD)") (class "Default")
      (node (ref "C9") (pin "2") (pinfunction "2_2") (pintype "passive"))
      (node (ref "IC2") (pin "1") (pinfunction "VDD_1") (pintype "passive"))
      (node (ref "R8") (pin "1") (pinfunction "1_1") (pintype "passive"))
    )
    (net (code "47") (name "Net-(R23-Pad2)") (class "Default")
      (node (ref "R23") (pin "2") (pinfunction "2_2") (pintype "passive"))
      (node (ref "R24") (pin "1") (pinfunction "1_1") (pintype "passive"))
    )
    (net (code "48") (name "Net-(U1-C1N)") (class "Default")
      (node (ref "C3") (pin "2") (pinfunction "2_2") (pintype "passive"))
      (node (ref "U1") (pin "5") (pinfunction "C1N_5") (pintype "passive"))
    )
    (net (code "49") (name "Net-(U1-C1P)") (class "Default")
      (node (ref "C3") (pin "1") (pinfunction "1_1") (pintype "passive"))
      (node (ref "U1") (pin "4") (pinfunction "C1P_4") (pintype "passive"))
    )
    (net (code "50") (name "Net-(U1-C2N)") (class "Default")
      (node (ref "C1") (pin "1") (pinfunction "1_1") (pintype "passive"))
      (node (ref "U1") (pin "3") (pinfunction "C2N_3") (pintype "passive"))
    )
    (net (code "51") (name "Net-(U1-C2P)") (class "Default")
      (node (ref "C1") (pin "2") (pinfunction "2_2") (pintype "passive"))
      (node (ref "U1") (pin "2") (pinfunction "C2P_2") (pintype "passive"))
    )
    (net (code "52") (name "Net-(U4-EN#)") (class "Default")
      (node (ref "R10") (pin "1") (pinfunction "1_1") (pintype "passive"))
      (node (ref "U4") (pin "9") (pinfunction "EN#_9") (pintype "passive"))
    )
    (net (code "53") (name "Net-(U4-IN)") (class "Default")
      (node (ref "R11") (pin "2") (pinfunction "2_2") (pintype "passive"))
      (node (ref "U4") (pin "1") (pinfunction "IN_1") (pintype "passive"))
    )
    (net (code "54") (name "Net-(U5-IN)") (class "Default")
      (node (ref "R15") (pin "2") (pinfunction "2_2") (pintype "passive"))
      (node (ref "U5") (pin "1") (pinfunction "IN_1") (pintype "passive"))
    )
    (net (code "55") (name "Net-(U7-BST)") (class "Default")
      (node (ref "C11") (pin "1") (pinfunction "1_1") (pintype "passive"))
      (node (ref "U7") (pin "6") (pinfunction "BST_6") (pintype "passive"))
    )
    (net (code "56") (name "Net-(U7-EN)") (class "Default")
      (node (ref "R17") (pin "2") (pinfunction "2_2") (pintype "passive"))
      (node (ref "U7") (pin "5") (pinfunction "EN_5") (pintype "passive"))
    )
    (net (code "57") (name "Net-(U7-FB)") (class "Default")
      (node (ref "R18") (pin "1") (pinfunction "1_1") (pintype "passive"))
      (node (ref "R19") (pin "1") (pinfunction "1_1") (pintype "passive"))
      (node (ref "U7") (pin "4") (pinfunction "FB_4") (pintype "passive"))
    )
    (net (code "58") (name "Net-(U7-SW)") (class "Default")
      (node (ref "C11") (pin "2") (pinfunction "2_2") (pintype "passive"))
      (node (ref "L1") (pin "2") (pinfunction "2_2") (pintype "passive"))
      (node (ref "U7") (pin "2") (pinfunction "SW_2") (pintype "passive"))
    )
    (net (code "59") (name "Net-(U8-BST)") (class "Default")
      (node (ref "C16") (pin "1") (pinfunction "1_1") (pintype "passive"))
      (node (ref "U8") (pin "6") (pinfunction "BST_6") (pintype "passive"))
    )
    (net (code "60") (name "Net-(U8-EN)") (class "Default")
      (node (ref "R22") (pin "2") (pinfunction "2_2") (pintype "passive"))
      (node (ref "U8") (pin "5") (pinfunction "EN_5") (pintype "passive"))
    )
    (net (code "61") (name "Net-(U8-FB)") (class "Default")
      (node (ref "R23") (pin "1") (pinfunction "1_1") (pintype "passive"))
      (node (ref "R26") (pin "1") (pinfunction "1_1") (pintype "passive"))
      (node (ref "U8") (pin "4") (pinfunction "FB_4") (pintype "passive"))
    )
    (net (code "62") (name "Net-(U8-SW)") (class "Default")
      (node (ref "C16") (pin "2") (pinfunction "2_2") (pintype "passive"))
      (node (ref "L2") (pin "2") (pinfunction "2_2") (pintype "passive"))
      (node (ref "U8") (pin "2") (pinfunction "SW_2") (pintype "passive"))
    )
    (net (code "63") (name "VBUS") (class "Default")
      (node (ref "C12") (pin "1") (pinfunction "1_1") (pintype "passive"))
      (node (ref "C13") (pin "1") (pinfunction "1_1") (pintype "passive"))
      (node (ref "P1") (pin "1") (pinfunction "M+_1") (pintype "passive"))
      (node (ref "R17") (pin "1") (pinfunction "1_1") (pintype "passive"))
      (node (ref "R20") (pin "1") (pinfunction "1_1") (pintype "passive"))
      (node (ref "R22") (pin "1") (pinfunction "1_1") (pintype "passive"))
      (node (ref "R8") (pin "2") (pinfunction "2_2") (pintype "passive"))
      (node (ref "R9") (pin "2") (pinfunction "2_2") (pintype "passive"))
      (node (ref "U7") (pin "3") (pinfunction "IN_3") (pintype "passive"))
      (node (ref "U8") (pin "3") (pinfunction "IN_3") (pintype "passive"))
      (node (ref "UART") (pin "A4") (pinfunction "VBUS_A_A4") (pintype "power_in"))
      (node (ref "UART") (pin "A9") (pinfunction "VBUS_A_A9") (pintype "power_in"))
      (node (ref "UART") (pin "B4") (pinfunction "VBUS_B_B4") (pintype "power_in"))
      (node (ref "UART") (pin "B9") (pinfunction "VBUS_B_B9") (pintype "power_in"))
    )
    (net (code "64") (name "unconnected-(*-IO22-Pad36)") (class "Default")
      (node (ref "*") (pin "36") (pinfunction "IO22_36") (pintype "bidirectional"))
    )
    (net (code "65") (name "unconnected-(*-IO23-Pad37)") (class "Default")
      (node (ref "*") (pin "37") (pinfunction "IO23_37") (pintype "bidirectional"))
    )
    (net (code "66") (name "unconnected-(*-IO34-Pad6)") (class "Default")
      (node (ref "*") (pin "6") (pinfunction "IO34_6") (pintype "input"))
    )
    (net (code "67") (name "unconnected-(*-NC-Pad32)") (class "Default")
      (node (ref "*") (pin "32") (pinfunction "NC_32") (pintype "passive"))
    )
    (net (code "68") (name "unconnected-(*-SCK-Pad20)") (class "Default")
      (node (ref "*") (pin "20") (pinfunction "SCK_20") (pintype "bidirectional"))
    )
    (net (code "69") (name "unconnected-(*-SCS-Pad19)") (class "Default")
      (node (ref "*") (pin "19") (pinfunction "SCS_19") (pintype "bidirectional"))
    )
    (net (code "70") (name "unconnected-(*-SDI-Pad22)") (class "Default")
      (node (ref "*") (pin "22") (pinfunction "SDI_22") (pintype "bidirectional"))
    )
    (net (code "71") (name "unconnected-(*-SDO-Pad21)") (class "Default")
      (node (ref "*") (pin "21") (pinfunction "SDO_21") (pintype "bidirectional"))
    )
    (net (code "72") (name "unconnected-(*-SENSOR_VN-Pad5)") (class "Default")
      (node (ref "*") (pin "5") (pinfunction "SENSOR_VN_5") (pintype "input"))
    )
    (net (code "73") (name "unconnected-(*-SENSOR_VP-Pad4)") (class "Default")
      (node (ref "*") (pin "4") (pinfunction "SENSOR_VP_4") (pintype "input"))
    )
    (net (code "74") (name "unconnected-(*-SHD-Pad17)") (class "Default")
      (node (ref "*") (pin "17") (pinfunction "SHD_17") (pintype "bidirectional"))
    )
    (net (code "75") (name "unconnected-(*-SWP-Pad18)") (class "Default")
      (node (ref "*") (pin "18") (pinfunction "SWP_18") (pintype "bidirectional"))
    )
    (net (code "76") (name "unconnected-(IC1-2A-Pad5)") (class "Default")
      (node (ref "IC1") (pin "5") (pinfunction "2A_5") (pintype "passive"))
    )
    (net (code "77") (name "unconnected-(IC1-2OE-Pad4)") (class "Default")
      (node (ref "IC1") (pin "4") (pinfunction "2OE_4") (pintype "passive"))
    )
    (net (code "78") (name "unconnected-(IC1-2Y-Pad6)") (class "Default")
      (node (ref "IC1") (pin "6") (pinfunction "2Y_6") (pintype "passive"))
    )
    (net (code "79") (name "unconnected-(IC1-GND-Pad7)") (class "Default")
      (node (ref "IC1") (pin "7") (pinfunction "GND_7") (pintype "passive"))
    )
    (net (code "80") (name "unconnected-(IC2-CFG1-Pad2)") (class "Default")
      (node (ref "IC2") (pin "2") (pinfunction "CFG1_2") (pintype "passive"))
    )
    (net (code "81") (name "unconnected-(IC2-CFG2-Pad3)") (class "Default")
      (node (ref "IC2") (pin "3") (pinfunction "CFG2_3") (pintype "passive"))
    )
    (net (code "82") (name "unconnected-(IC2-CFG3-Pad9)") (class "Default")
      (node (ref "IC2") (pin "9") (pinfunction "CFG3_9") (pintype "passive"))
    )
    (net (code "83") (name "unconnected-(IC2-PG-Pad10)") (class "Default")
      (node (ref "IC2") (pin "10") (pinfunction "PG_10") (pintype "passive"))
    )
    (net (code "84") (name "unconnected-(U1-NC-Pad7)") (class "Default")
      (node (ref "U1") (pin "7") (pinfunction "NC_7") (pintype "passive"))
    )
    (net (code "85") (name "unconnected-(U2-PAD-Pad10)") (class "Default")
      (node (ref "U2") (pin "10") (pinfunction "PAD_10") (pintype "passive"))
    )
    (net (code "86") (name "unconnected-(U2-PAD-Pad11)") (class "Default")
      (node (ref "U2") (pin "11") (pinfunction "PAD_11") (pintype "passive"))
    )
    (net (code "87") (name "unconnected-(U2-PAD-Pad12)") (class "Default")
      (node (ref "U2") (pin "12") (pinfunction "PAD_12") (pintype "passive"))
    )
    (net (code "88") (name "unconnected-(U2-PAD-Pad13)") (class "Default")
      (node (ref "U2") (pin "13") (pinfunction "PAD_13") (pintype "passive"))
    )
    (net (code "89") (name "unconnected-(U3-G-Pad7)") (class "Default")
      (node (ref "U3") (pin "7") (pinfunction "G_7") (pintype "passive"))
    )
    (net (code "90") (name "unconnected-(U3-G-Pad8)") (class "Default")
      (node (ref "U3") (pin "8") (pinfunction "G_8") (pintype "passive"))
    )
    (net (code "91") (name "unconnected-(U3-Pad3)") (class "Default")
      (node (ref "U3") (pin "3") (pintype "passive"))
    )
    (net (code "92") (name "unconnected-(U3-Pad5)") (class "Default")
      (node (ref "U3") (pin "5") (pintype "passive"))
    )
    (net (code "93") (name "unconnected-(U3-Pad9)") (class "Default")
      (node (ref "U3") (pin "9") (pintype "passive"))
    )
    (net (code "94") (name "unconnected-(U3-Pad10)") (class "Default")
      (node (ref "U3") (pin "10") (pintype "passive"))
    )
    (net (code "95") (name "unconnected-(U5-S1C-Pad8)") (class "Default")
      (node (ref "U5") (pin "8") (pinfunction "S1C_8") (pintype "passive"))
    )
    (net (code "96") (name "unconnected-(U6-RTS#-Pad4)") (class "Default")
      (node (ref "U6") (pin "4") (pinfunction "RTS#_4") (pintype "passive"))
    )
    (net (code "97") (name "unconnected-(UART-SBU1-PadA8)") (class "Default")
      (node (ref "UART") (pin "A8") (pinfunction "SBU1_A8") (pintype "bidirectional"))
    )
    (net (code "98") (name "unconnected-(UART-SBU2-PadB8)") (class "Default")
      (node (ref "UART") (pin "B8") (pinfunction "SBU2_B8") (pintype "bidirectional"))
    )
  )
)
